# CAN_PHY.net
KiCad netlist of a schematic drawn in Altium Designer
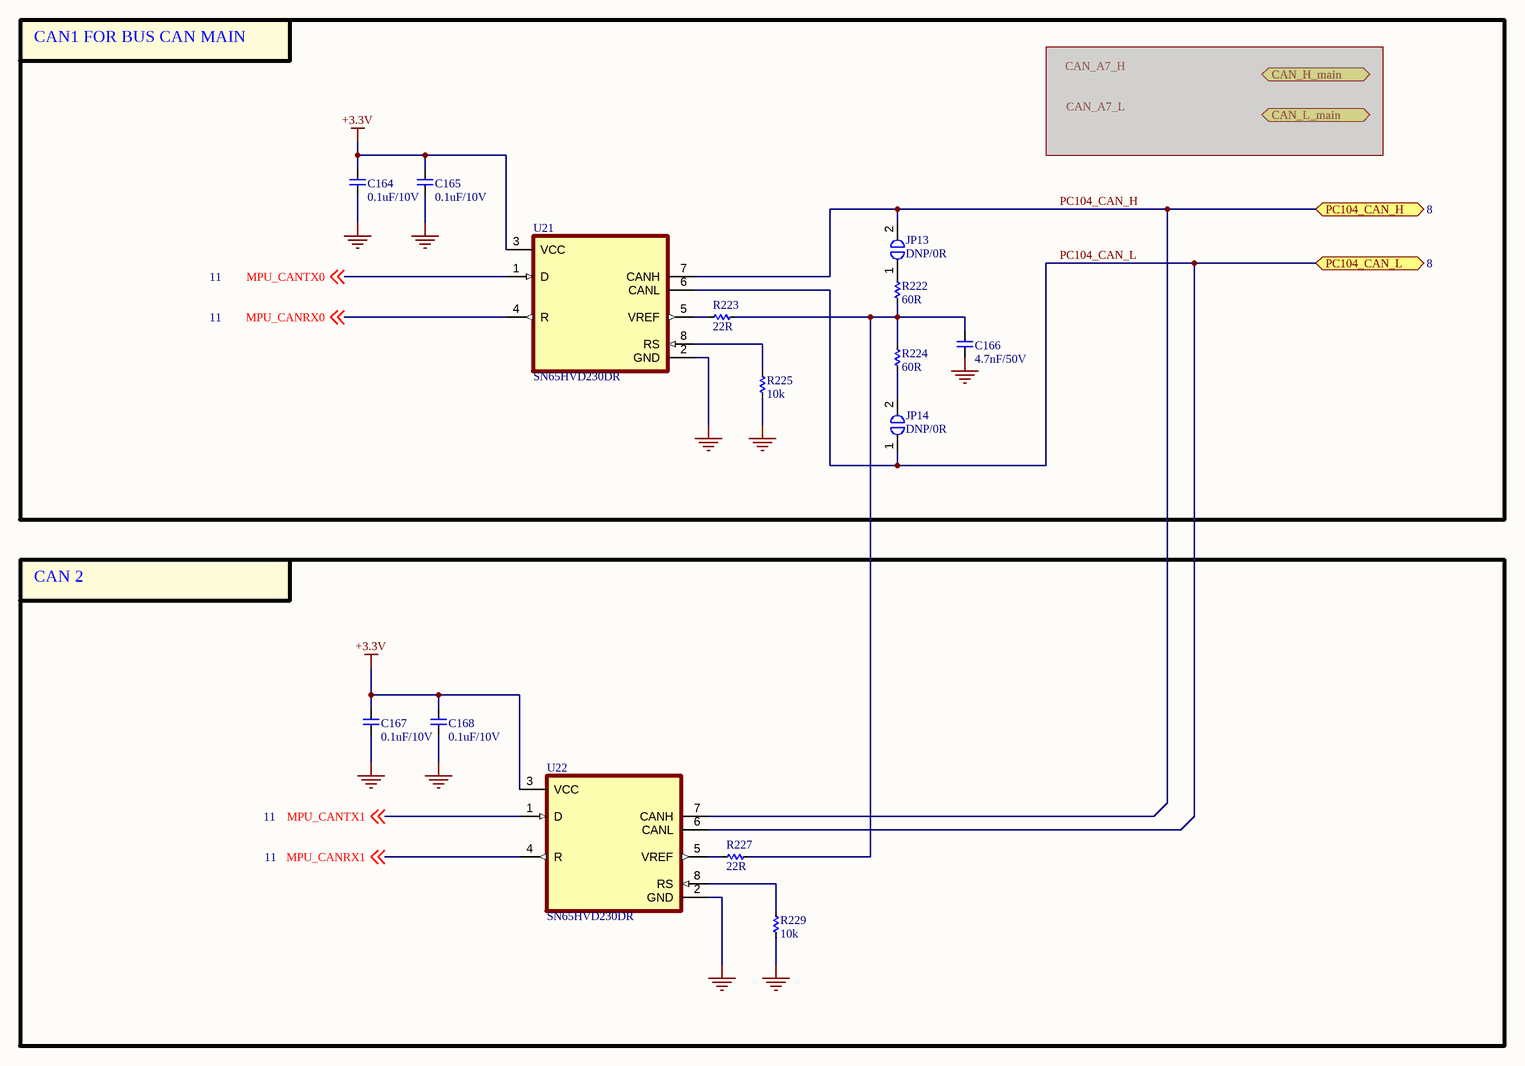
[diagram p0: CAN_PHY.SchDoc]

(export (version "E")
  (design (tool "Eeschema 10.0.6"))
  (components
    (comp (ref "C164")
      (value "0.1uF/10V")
      (footprint "CAP_C_1005X50_L")
      (description "CAP")
      (libsource (lib "LABLIB") (part "_CAP_C_2"))
    )
    (comp (ref "C165")
      (value "0.1uF/10V")
      (footprint "CAP_C_1005X50_L")
      (description "CAP")
      (libsource (lib "LABLIB") (part "_CAP_C_2"))
    )
    (comp (ref "C166")
      (value "4.7nF/50V")
      (footprint "CAP_C_1608X80")
      (description "CAP")
      (libsource (lib "LABLIB") (part "_CAP_C_2"))
    )
    (comp (ref "C167")
      (value "0.1uF/10V")
      (footprint "CAP_C_1005X50_L")
      (description "CAP")
      (libsource (lib "LABLIB") (part "_CAP_C_2"))
    )
    (comp (ref "C168")
      (value "0.1uF/10V")
      (footprint "CAP_C_1005X50_L")
      (description "CAP")
      (libsource (lib "LABLIB") (part "_CAP_C_2"))
    )
    (comp (ref "JP13")
      (value "DNP/0R")
      (footprint "RES_C_1608X60")
      (libsource (lib "LABLIB") (part "JUMPER_1_1"))
    )
    (comp (ref "JP14")
      (value "DNP/0R")
      (footprint "RES_C_1608X60")
      (libsource (lib "LABLIB") (part "JUMPER_1_1"))
    )
    (comp (ref "R222")
      (value "60R")
      (footprint "RES_C_1005x30_L")
      (description "RES")
      (libsource (lib "IFBschelib") (part "_RES_B_2"))
    )
    (comp (ref "R223")
      (value "22R")
      (footprint "RES_C_1005x30_L")
      (description "RES")
      (libsource (lib "LABLIB") (part "_RES_B_2"))
    )
    (comp (ref "R224")
      (value "60R")
      (footprint "RES_C_1005x30_L")
      (description "RES")
      (libsource (lib "IFBschelib") (part "_RES_B_2"))
    )
    (comp (ref "R225")
      (value "10k")
      (footprint "RES_C_1005x30_L")
      (description "RES")
      (libsource (lib "LABLIB") (part "_RES_B_2"))
    )
    (comp (ref "R227")
      (value "22R")
      (footprint "RES_C_1005x30_L")
      (description "RES")
      (libsource (lib "LABLIB") (part "_RES_B_2"))
    )
    (comp (ref "R229")
      (value "10k")
      (footprint "RES_C_1005x30_L")
      (description "RES")
      (libsource (lib "LABLIB") (part "_RES_B_2"))
    )
    (comp (ref "U21")
      (value "SN65HVD230DR")
      (footprint "SOIC127P602X173-8N")
      (description "3.3 V CAN Transceiver with Standby Mode")
      (fields (field (name "MF") "Texas Instruments"))
      (libsource (lib "IFBschelib") (part "SN65HVD230DR"))
    )
    (comp (ref "U22")
      (value "SN65HVD230DR")
      (footprint "SOIC127P602X173-8N")
      (description "3.3 V CAN Transceiver with Standby Mode")
      (fields (field (name "MF") "Texas Instruments"))
      (libsource (lib "IFBschelib") (part "SN65HVD230DR"))
    )
  )
  (nets
    (net (code "1") (name "+3.3V") (class "Default")
      (node (ref "C164") (pin "2") (pinfunction "2_2") (pintype "passive"))
      (node (ref "C165") (pin "2") (pinfunction "2_2") (pintype "passive"))
      (node (ref "C167") (pin "2") (pinfunction "2_2") (pintype "passive"))
      (node (ref "C168") (pin "2") (pinfunction "2_2") (pintype "passive"))
      (node (ref "U21") (pin "3") (pinfunction "VCC_3") (pintype "power_in"))
      (node (ref "U22") (pin "3") (pinfunction "VCC_3") (pintype "power_in"))
    )
    (net (code "6") (name "/PC104_CAN_H") (class "Default")
      (node (ref "JP13") (pin "2") (pinfunction "2_2") (pintype "passive"))
      (node (ref "U21") (pin "7") (pinfunction "CANH_7") (pintype "passive"))
      (node (ref "U22") (pin "7") (pinfunction "CANH_7") (pintype "passive"))
    )
    (net (code "7") (name "/PC104_CAN_L") (class "Default")
      (node (ref "JP14") (pin "1") (pinfunction "1_1") (pintype "passive"))
      (node (ref "U21") (pin "6") (pinfunction "CANL_6") (pintype "passive"))
      (node (ref "U22") (pin "6") (pinfunction "CANL_6") (pintype "passive"))
    )
    (net (code "8") (name "GND") (class "Default")
      (node (ref "C164") (pin "1") (pinfunction "1_1") (pintype "passive"))
      (node (ref "C165") (pin "1") (pinfunction "1_1") (pintype "passive"))
      (node (ref "C166") (pin "1") (pinfunction "1_1") (pintype "passive"))
      (node (ref "C167") (pin "1") (pinfunction "1_1") (pintype "passive"))
      (node (ref "C168") (pin "1") (pinfunction "1_1") (pintype "passive"))
      (node (ref "R225") (pin "2") (pinfunction "2_2") (pintype "passive"))
      (node (ref "R229") (pin "2") (pinfunction "2_2") (pintype "passive"))
      (node (ref "U21") (pin "2") (pinfunction "GND_2") (pintype "power_in"))
      (node (ref "U22") (pin "2") (pinfunction "GND_2") (pintype "power_in"))
    )
    (net (code "9") (name "MPU_CANRX0") (class "Default")
      (node (ref "U21") (pin "4") (pinfunction "R_4") (pintype "output"))
    )
    (net (code "10") (name "MPU_CANRX1") (class "Default")
      (node (ref "U22") (pin "4") (pinfunction "R_4") (pintype "output"))
    )
    (net (code "11") (name "MPU_CANTX0") (class "Default")
      (node (ref "U21") (pin "1") (pinfunction "D_1") (pintype "input"))
    )
    (net (code "12") (name "MPU_CANTX1") (class "Default")
      (node (ref "U22") (pin "1") (pinfunction "D_1") (pintype "input"))
    )
    (net (code "13") (name "Net-(C166-Pad2)") (class "Default")
      (node (ref "C166") (pin "2") (pinfunction "2_2") (pintype "passive"))
      (node (ref "R222") (pin "2") (pinfunction "2_2") (pintype "passive"))
      (node (ref "R223") (pin "1") (pinfunction "1_1") (pintype "passive"))
      (node (ref "R224") (pin "1") (pinfunction "1_1") (pintype "passive"))
      (node (ref "R227") (pin "1") (pinfunction "1_1") (pintype "passive"))
    )
    (net (code "14") (name "Net-(JP13-Pad1)") (class "Default")
      (node (ref "JP13") (pin "1") (pinfunction "1_1") (pintype "passive"))
      (node (ref "R222") (pin "1") (pinfunction "1_1") (pintype "passive"))
    )
    (net (code "15") (name "Net-(JP14-Pad2)") (class "Default")
      (node (ref "JP14") (pin "2") (pinfunction "2_2") (pintype "passive"))
      (node (ref "R224") (pin "2") (pinfunction "2_2") (pintype "passive"))
    )
    (net (code "16") (name "Net-(U21-RS)") (class "Default")
      (node (ref "R225") (pin "1") (pinfunction "1_1") (pintype "passive"))
      (node (ref "U21") (pin "8") (pinfunction "RS_8") (pintype "input"))
    )
    (net (code "17") (name "Net-(U21-VREF)") (class "Default")
      (node (ref "R223") (pin "2") (pinfunction "2_2") (pintype "passive"))
      (node (ref "U21") (pin "5") (pinfunction "VREF_5") (pintype "output"))
    )
    (net (code "18") (name "Net-(U22-RS)") (class "Default")
      (node (ref "R229") (pin "1") (pinfunction "1_1") (pintype "passive"))
      (node (ref "U22") (pin "8") (pinfunction "RS_8") (pintype "input"))
    )
    (net (code "19") (name "Net-(U22-VREF)") (class "Default")
      (node (ref "R227") (pin "2") (pinfunction "2_2") (pintype "passive"))
      (node (ref "U22") (pin "5") (pinfunction "VREF_5") (pintype "output"))
    )
  )
)
